# RJ45Split.net
KiCad netlist of a schematic drawn in EAGLE
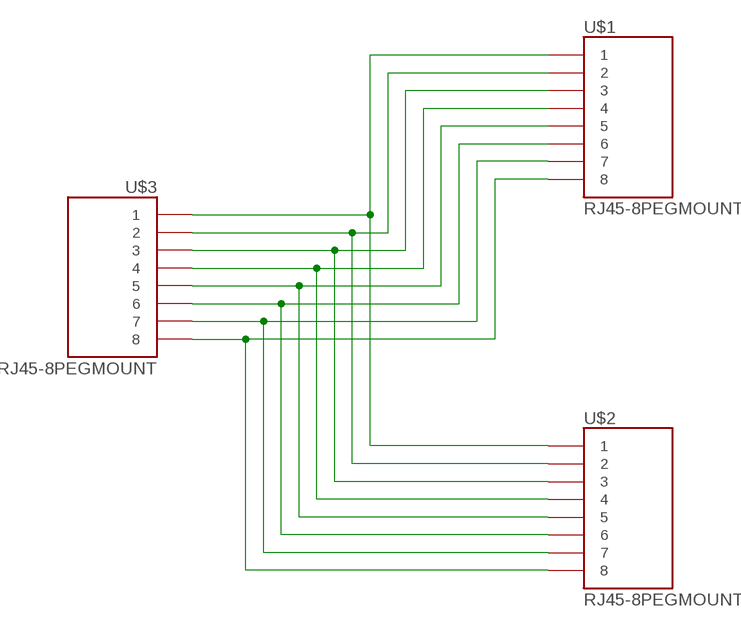
[diagram p0: schematic, sheet 1]

(export (version "E")
  (design (tool "Eeschema 10.0.6"))
  (components
    (comp (ref "U$1")
      (value "RJ45-8PEGMOUNT")
      (footprint "eagle-import:MOLEX-0955016889")
      (libsource (lib "eagle-import") (part "RJ45-8PEGMOUNT"))
    )
    (comp (ref "U$2")
      (value "RJ45-8PEGMOUNT")
      (footprint "eagle-import:MOLEX-0955016889")
      (libsource (lib "eagle-import") (part "RJ45-8PEGMOUNT"))
    )
    (comp (ref "U$3")
      (value "RJ45-8PEGMOUNT")
      (footprint "eagle-import:MOLEX-0955016889")
      (libsource (lib "eagle-import") (part "RJ45-8PEGMOUNT"))
    )
  )
  (nets
    (net (code "1") (name "Net-(U$1-1)") (class "Default")
      (node (ref "U$1") (pin "P$1") (pinfunction "1_P$1") (pintype "bidirectional"))
      (node (ref "U$2") (pin "P$1") (pinfunction "1_P$1") (pintype "bidirectional"))
      (node (ref "U$3") (pin "P$1") (pinfunction "1_P$1") (pintype "bidirectional"))
    )
    (net (code "2") (name "Net-(U$1-2)") (class "Default")
      (node (ref "U$1") (pin "P$2") (pinfunction "2_P$2") (pintype "bidirectional"))
      (node (ref "U$2") (pin "P$2") (pinfunction "2_P$2") (pintype "bidirectional"))
      (node (ref "U$3") (pin "P$2") (pinfunction "2_P$2") (pintype "bidirectional"))
    )
    (net (code "3") (name "Net-(U$1-3)") (class "Default")
      (node (ref "U$1") (pin "P$3") (pinfunction "3_P$3") (pintype "bidirectional"))
      (node (ref "U$2") (pin "P$3") (pinfunction "3_P$3") (pintype "bidirectional"))
      (node (ref "U$3") (pin "P$3") (pinfunction "3_P$3") (pintype "bidirectional"))
    )
    (net (code "4") (name "Net-(U$1-4)") (class "Default")
      (node (ref "U$1") (pin "P$4") (pinfunction "4_P$4") (pintype "bidirectional"))
      (node (ref "U$2") (pin "P$4") (pinfunction "4_P$4") (pintype "bidirectional"))
      (node (ref "U$3") (pin "P$4") (pinfunction "4_P$4") (pintype "bidirectional"))
    )
    (net (code "5") (name "Net-(U$1-5)") (class "Default")
      (node (ref "U$1") (pin "P$5") (pinfunction "5_P$5") (pintype "bidirectional"))
      (node (ref "U$2") (pin "P$5") (pinfunction "5_P$5") (pintype "bidirectional"))
      (node (ref "U$3") (pin "P$5") (pinfunction "5_P$5") (pintype "bidirectional"))
    )
    (net (code "6") (name "Net-(U$1-6)") (class "Default")
      (node (ref "U$1") (pin "P$6") (pinfunction "6_P$6") (pintype "bidirectional"))
      (node (ref "U$2") (pin "P$6") (pinfunction "6_P$6") (pintype "bidirectional"))
      (node (ref "U$3") (pin "P$6") (pinfunction "6_P$6") (pintype "bidirectional"))
    )
    (net (code "7") (name "Net-(U$1-7)") (class "Default")
      (node (ref "U$1") (pin "P$7") (pinfunction "7_P$7") (pintype "bidirectional"))
      (node (ref "U$2") (pin "P$7") (pinfunction "7_P$7") (pintype "bidirectional"))
      (node (ref "U$3") (pin "P$7") (pinfunction "7_P$7") (pintype "bidirectional"))
    )
    (net (code "8") (name "Net-(U$1-8)") (class "Default")
      (node (ref "U$1") (pin "P$8") (pinfunction "8_P$8") (pintype "bidirectional"))
      (node (ref "U$2") (pin "P$8") (pinfunction "8_P$8") (pintype "bidirectional"))
      (node (ref "U$3") (pin "P$8") (pinfunction "8_P$8") (pintype "bidirectional"))
    )
  )
)
